# CAN_5V0.net
KiCad netlist of a schematic drawn in Altium Designer
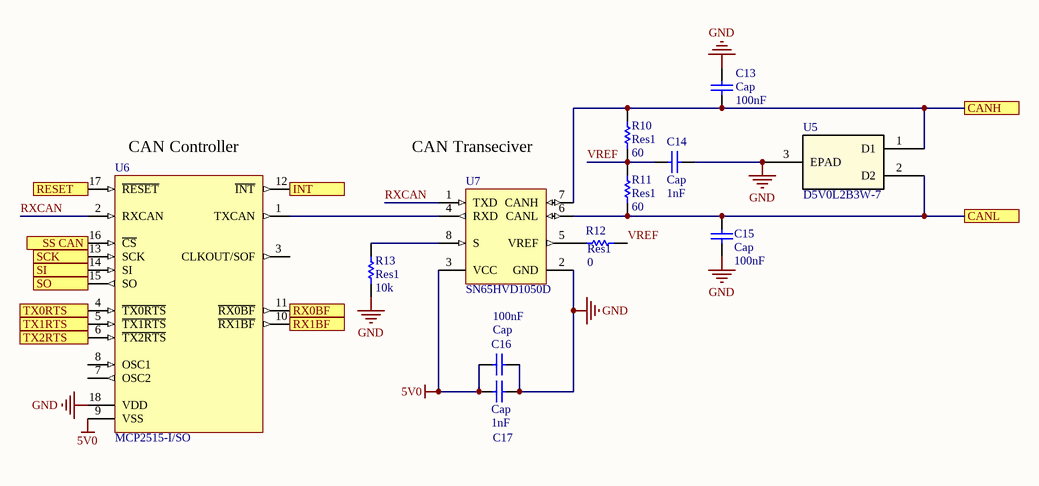
[diagram p0: CAN 5V0.SchDoc]

(export (version "E")
  (design (tool "Eeschema 10.0.6"))
  (components
    (comp (ref "C13")
      (value "Cap")
      (footprint "RAD-0.3")
      (description "Capacitor")
      (fields (field (name "ALTIUM_VALUE") "100nF") (field (name "PUBLISHER") "Altium Limited"))
      (libsource (lib "Miscellaneous Devices") (part "Cap"))
    )
    (comp (ref "C14")
      (value "Cap")
      (footprint "RAD-0.3")
      (description "Capacitor")
      (fields (field (name "ALTIUM_VALUE") "1nF") (field (name "PUBLISHER") "Altium Limited"))
      (libsource (lib "Miscellaneous Devices") (part "Cap"))
    )
    (comp (ref "C15")
      (value "Cap")
      (footprint "RAD-0.3")
      (description "Capacitor")
      (fields (field (name "ALTIUM_VALUE") "100nF") (field (name "PUBLISHER") "Altium Limited"))
      (libsource (lib "Miscellaneous Devices") (part "Cap"))
    )
    (comp (ref "C16")
      (value "Cap")
      (footprint "RAD-0.3")
      (description "Capacitor")
      (fields (field (name "ALTIUM_VALUE") "100nF") (field (name "PUBLISHER") "Altium Limited"))
      (libsource (lib "Miscellaneous Devices") (part "Cap"))
    )
    (comp (ref "C17")
      (value "Cap")
      (footprint "RAD-0.3")
      (description "Capacitor")
      (fields (field (name "ALTIUM_VALUE") "1nF") (field (name "PUBLISHER") "Altium Limited"))
      (libsource (lib "Miscellaneous Devices") (part "Cap"))
    )
    (comp (ref "R10")
      (value "Res1")
      (footprint "AXIAL-0.3")
      (description "Resistor")
      (fields (field (name "ALTIUM_VALUE") "60") (field (name "PUBLISHER") "Altium Limited"))
      (libsource (lib "Miscellaneous Devices") (part "Res1"))
    )
    (comp (ref "R11")
      (value "Res1")
      (footprint "AXIAL-0.3")
      (description "Resistor")
      (fields (field (name "ALTIUM_VALUE") "60") (field (name "PUBLISHER") "Altium Limited"))
      (libsource (lib "Miscellaneous Devices") (part "Res1"))
    )
    (comp (ref "R12")
      (value "Res1")
      (footprint "AXIAL-0.3")
      (description "Resistor")
      (fields (field (name "ALTIUM_VALUE") "0") (field (name "PUBLISHER") "Altium Limited"))
      (libsource (lib "Miscellaneous Devices") (part "Res1"))
    )
    (comp (ref "R13")
      (value "Res1")
      (footprint "AXIAL-0.3")
      (description "Resistor")
      (fields (field (name "ALTIUM_VALUE") "10k") (field (name "PUBLISHER") "Altium Limited"))
      (libsource (lib "Miscellaneous Devices") (part "Res1"))
    )
    (comp (ref "U5")
      (value "D5V0L2B3W-7")
      (footprint "SOT-323_DIO")
      (description "No Description Available")
      (fields (field (name "COPYRIGHT") "Copyright (C) 2018 Accelerated Designs. All rights reserved"))
      (libsource (lib "D5V0L2B3W-7 library") (part "D5V0L2B3W-7"))
    )
    (comp (ref "U6")
      (value "MCP2515-I/SO")
      (footprint "SOIC-SO18_L")
      (description "Stand-Alone CAN Controller With SPI Interface, 18-Pin SOIC, Industrial Temperature")
      (libsource (lib "Altium Content Vault") (part "COM-CAN-MCP2515-18"))
    )
    (comp (ref "U7")
      (value "SN65HVD1050D")
      (footprint "D0008A_N")
      (fields (field (name "MANUFACTURER") "Texas Instruments"))
      (libsource (lib "Altium Content Vault") (part "TI-SN65HVD1050-SOIC_D-8"))
    )
  )
  (nets
    (net (code "1") (name "/CANH") (class "Default")
      (node (ref "C13") (pin "2") (pinfunction "2_2") (pintype "passive"))
      (node (ref "R10") (pin "1") (pinfunction "1_1") (pintype "passive"))
      (node (ref "U5") (pin "1") (pinfunction "D1_1") (pintype "passive"))
      (node (ref "U7") (pin "7") (pinfunction "CANH_7") (pintype "bidirectional"))
    )
    (net (code "2") (name "/CANL") (class "Default")
      (node (ref "C15") (pin "2") (pinfunction "2_2") (pintype "passive"))
      (node (ref "R11") (pin "1") (pinfunction "1_1") (pintype "passive"))
      (node (ref "U5") (pin "2") (pinfunction "D2_2") (pintype "passive"))
      (node (ref "U7") (pin "6") (pinfunction "CANL_6") (pintype "bidirectional"))
    )
    (net (code "3") (name "/INT") (class "Default")
      (node (ref "U6") (pin "12") (pinfunction "~{INT}_12") (pintype "output"))
    )
    (net (code "4") (name "/RESET") (class "Default")
      (node (ref "U6") (pin "17") (pinfunction "~{RESET}_17") (pintype "input"))
    )
    (net (code "5") (name "/RX0BF") (class "Default")
      (node (ref "U6") (pin "11") (pinfunction "~{RX0BF}_11") (pintype "output"))
    )
    (net (code "6") (name "/RX1BF") (class "Default")
      (node (ref "U6") (pin "10") (pinfunction "~{RX1BF}_10") (pintype "output"))
    )
    (net (code "7") (name "/RXCAN") (class "Default")
      (node (ref "U6") (pin "2") (pinfunction "RXCAN_2") (pintype "input"))
      (node (ref "U7") (pin "1") (pinfunction "TXD_1") (pintype "input"))
    )
    (net (code "8") (name "/SCK") (class "Default")
      (node (ref "U6") (pin "13") (pinfunction "SCK_13") (pintype "input"))
    )
    (net (code "9") (name "/SI") (class "Default")
      (node (ref "U6") (pin "14") (pinfunction "SI_14") (pintype "input"))
    )
    (net (code "10") (name "/SO") (class "Default")
      (node (ref "U6") (pin "15") (pinfunction "SO_15") (pintype "output"))
    )
    (net (code "11") (name "/SS CAN") (class "Default")
      (node (ref "U6") (pin "16") (pinfunction "~{CS}_16") (pintype "input"))
    )
    (net (code "12") (name "/TX0RTS") (class "Default")
      (node (ref "U6") (pin "4") (pinfunction "~{TX0RTS}_4") (pintype "input"))
    )
    (net (code "13") (name "/TX1RTS") (class "Default")
      (node (ref "U6") (pin "5") (pinfunction "~{TX1RTS}_5") (pintype "input"))
    )
    (net (code "14") (name "/TX2RTS") (class "Default")
      (node (ref "U6") (pin "6") (pinfunction "~{TX2RTS}_6") (pintype "input"))
    )
    (net (code "15") (name "/VREF") (class "Default")
      (node (ref "C14") (pin "1") (pinfunction "1_1") (pintype "passive"))
      (node (ref "R10") (pin "2") (pinfunction "2_2") (pintype "passive"))
      (node (ref "R11") (pin "2") (pinfunction "2_2") (pintype "passive"))
      (node (ref "R12") (pin "2") (pinfunction "2_2") (pintype "passive"))
    )
    (net (code "16") (name "5V0") (class "Default")
      (node (ref "C16") (pin "1") (pinfunction "1_1") (pintype "passive"))
      (node (ref "C17") (pin "2") (pinfunction "2_2") (pintype "passive"))
      (node (ref "U6") (pin "9") (pinfunction "VSS_9") (pintype "power_in"))
      (node (ref "U7") (pin "3") (pinfunction "VCC_3") (pintype "power_in"))
    )
    (net (code "17") (name "GND") (class "Default")
      (node (ref "C13") (pin "1") (pinfunction "1_1") (pintype "passive"))
      (node (ref "C14") (pin "2") (pinfunction "2_2") (pintype "passive"))
      (node (ref "C15") (pin "1") (pinfunction "1_1") (pintype "passive"))
      (node (ref "C16") (pin "2") (pinfunction "2_2") (pintype "passive"))
      (node (ref "C17") (pin "1") (pinfunction "1_1") (pintype "passive"))
      (node (ref "R13") (pin "1") (pinfunction "1_1") (pintype "passive"))
      (node (ref "U5") (pin "3") (pinfunction "EPAD_3") (pintype "passive"))
      (node (ref "U6") (pin "18") (pinfunction "VDD_18") (pintype "power_in"))
      (node (ref "U7") (pin "2") (pinfunction "GND_2") (pintype "power_in"))
    )
    (net (code "18") (name "Net-(U6-TXCAN)") (class "Default")
      (node (ref "U6") (pin "1") (pinfunction "TXCAN_1") (pintype "output"))
      (node (ref "U7") (pin "4") (pinfunction "RXD_4") (pintype "output"))
    )
    (net (code "19") (name "Net-(U7-S)") (class "Default")
      (node (ref "R13") (pin "2") (pinfunction "2_2") (pintype "passive"))
      (node (ref "U7") (pin "8") (pinfunction "S_8") (pintype "input"))
    )
    (net (code "20") (name "Net-(U7-VREF)") (class "Default")
      (node (ref "R12") (pin "1") (pinfunction "1_1") (pintype "passive"))
      (node (ref "U7") (pin "5") (pinfunction "VREF_5") (pintype "output"))
    )
    (net (code "21") (name "unconnected-(U6-CLKOUT{slash}SOF-Pad3)") (class "Default")
      (node (ref "U6") (pin "3") (pinfunction "CLKOUT/SOF_3") (pintype "output"))
    )
    (net (code "22") (name "unconnected-(U6-OSC1-Pad8)") (class "Default")
      (node (ref "U6") (pin "8") (pinfunction "OSC1_8") (pintype "input"))
    )
    (net (code "23") (name "unconnected-(U6-OSC2-Pad7)") (class "Default")
      (node (ref "U6") (pin "7") (pinfunction "OSC2_7") (pintype "output"))
    )
  )
)
